# esp32.net
KiCad netlist of a schematic drawn in Altium Designer
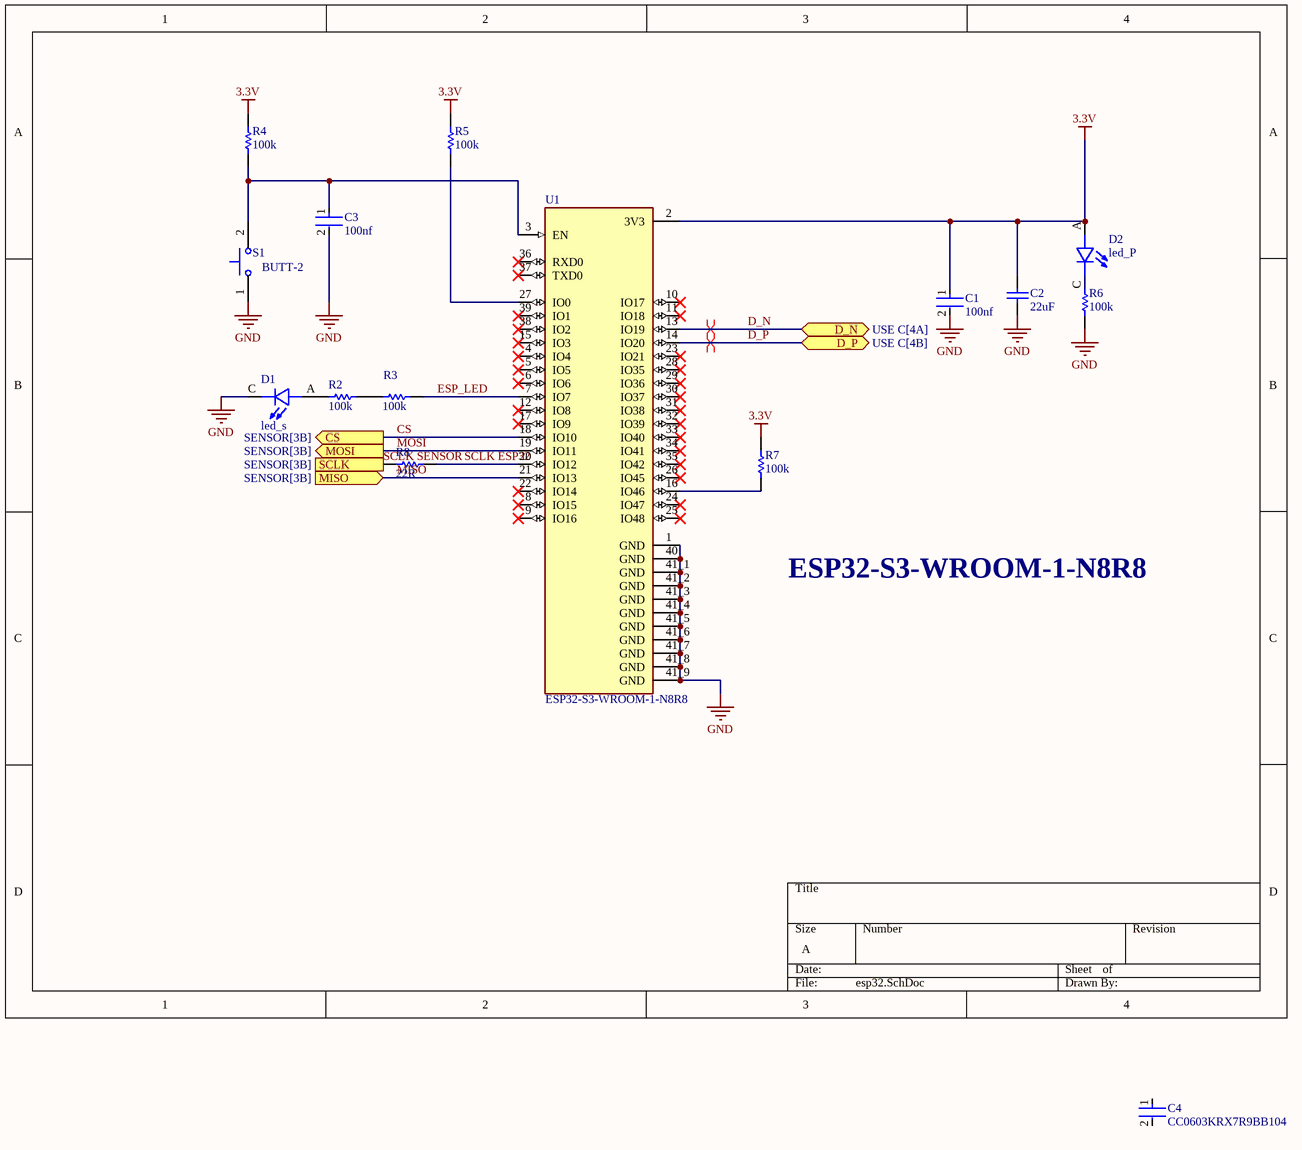
[diagram p0: esp32.SchDoc]

(export (version "E")
  (design (tool "Eeschema 10.0.6"))
  (components
    (comp (ref "C1")
      (value "100nf")
      (footprint "FP-CC0603-DA-MFG")
      (description "CAP CER 0.1UF 50V X7R 0603")
      (fields (field (name "MANUFACTURER") "YAGEO") (field (name "VOLTAGE") "50 V"))
      (libsource (lib "Altium Content Vault") (part "11868f565c42a9108669ba33697ecf6"))
    )
    (comp (ref "C2")
      (value "22uF")
      (footprint "CAPC3216X180X55ML20T25")
      (description "Chip Capacitor, 22 uF, +/- 10%, 25 V, -55 to 85 degC, 1206 (3216 Metric), RoHS, Tape and Reel")
      (fields (field (name "PARTNUMBER") "GRM31CR61E226KE15L") (field (name "TOLERANCE") "10%"))
      (libsource (lib "Altium Content Vault") (part "CAP-NP-2"))
    )
    (comp (ref "C3")
      (value "100nf")
      (footprint "FP-CC0603-DA-MFG")
      (description "CAP CER 0.1UF 50V X7R 0603")
      (fields (field (name "MANUFACTURER") "YAGEO") (field (name "VOLTAGE") "50 V"))
      (libsource (lib "Altium Content Vault") (part "11868f565c42a9108669ba33697ecf6"))
    )
    (comp (ref "C4")
      (value "CC0603KRX7R9BB104")
      (footprint "FP-CC0603-DA-MFG")
      (description "CAP CER 0.1UF 50V X7R 0603")
      (fields (field (name "MANUFACTURER") "YAGEO") (field (name "VOLTAGE") "50 V"))
      (libsource (lib "Altium Content Vault") (part "11868f565c42a9108669ba33697ecf6"))
    )
    (comp (ref "D1")
      (value "led_s")
      (footprint "LEDRD254W57D500H1070")
      (fields (field (name "MP") "L08R5000Q1") (field (name "MF") "LED Technology"))
      (libsource (lib "L08R5000Q1") (part "L08R5000Q1"))
    )
    (comp (ref "D2")
      (value "led_P")
      (footprint "LEDRD254W57D500H1070")
      (fields (field (name "MP") "L08R5000Q1") (field (name "MF") "LED Technology"))
      (libsource (lib "L08R5000Q1") (part "L08R5000Q1"))
    )
    (comp (ref "R2")
      (value "100k")
      (footprint "RESC1005X40X25NL05T10")
      (fields (field (name "PART NUMBER") "RC0402FR-07100KL") (field (name "MANUFACTURER") "Yageo / Phycomp"))
      (libsource (lib "Altium Content Vault") (part "RES"))
    )
    (comp (ref "R3")
      (value "100k")
      (footprint "RESC1005X40X25NL05T10")
      (fields (field (name "PART NUMBER") "RC0402FR-07100KL") (field (name "MANUFACTURER") "Yageo / Phycomp"))
      (libsource (lib "Altium Content Vault") (part "RES"))
    )
    (comp (ref "R4")
      (value "100k")
      (footprint "RESC1005X40X25NL05T10")
      (fields (field (name "PART NUMBER") "RC0402FR-07100KL") (field (name "MANUFACTURER") "Yageo / Phycomp"))
      (libsource (lib "Altium Content Vault") (part "RES"))
    )
    (comp (ref "R5")
      (value "100k")
      (footprint "RESC1005X40X25NL05T10")
      (fields (field (name "PART NUMBER") "RC0402FR-07100KL") (field (name "MANUFACTURER") "Yageo / Phycomp"))
      (libsource (lib "Altium Content Vault") (part "RES"))
    )
    (comp (ref "R6")
      (value "100k")
      (footprint "RESC1005X40X25NL05T10")
      (fields (field (name "PART NUMBER") "RC0402FR-07100KL") (field (name "MANUFACTURER") "Yageo / Phycomp"))
      (libsource (lib "Altium Content Vault") (part "RES"))
    )
    (comp (ref "R7")
      (value "100k")
      (footprint "RESC1005X40X25NL05T10")
      (fields (field (name "PART NUMBER") "RC0402FR-07100KL") (field (name "MANUFACTURER") "Yageo / Phycomp"))
      (libsource (lib "Altium Content Vault") (part "RES"))
    )
    (comp (ref "R8")
      (value "22R")
      (footprint "RESC1608X55X25NL10T15")
      (description "Chip Resistor, 22 Ohm, +/- 1%, 0.1 W, -55 to 155 degC, 0603 (1608 Metric), RoHS, Tape and Reel")
      (libsource (lib "Altium Content Vault") (part "RES-2"))
    )
    (comp (ref "S1")
      (value "BUTT-2")
      (footprint "SW_BUTT-2")
      (description "Tactile Switches MINI PUSH BUTTON SWITCH 2-PIN QTY. 4")
      (fields (field (name "MF") "Gravitech"))
      (libsource (lib "BUTT-2") (part "BUTT-2"))
    )
    (comp (ref "U1")
      (value "ESP32-S3-WROOM-1-N8R8")
      (footprint "XCVR_ESP32S3WROOM1N8R8")
      (description "Bluetooth, WiFi 802.11b/g/n, Bluetooth v5.0 Transceiver Module 2.4GHz PCB Trace Surface Mount")
      (fields (field (name "MF") "Espressif Systems"))
      (libsource (lib "ESP32-S3-WROOM-1-N8R8") (part "ESP32-S3-WROOM-1-N8R8"))
    )
  )
  (nets
    (net (code "1") (name "/CS") (class "Default")
      (node (ref "U1") (pin "18") (pinfunction "IO10_18") (pintype "bidirectional"))
    )
    (net (code "2") (name "/D_N") (class "Default")
      (node (ref "U1") (pin "13") (pinfunction "IO19_13") (pintype "bidirectional"))
    )
    (net (code "3") (name "/D_P") (class "Default")
      (node (ref "U1") (pin "14") (pinfunction "IO20_14") (pintype "bidirectional"))
    )
    (net (code "4") (name "/ESP_LED") (class "Default")
      (node (ref "R3") (pin "1") (pinfunction "1_1") (pintype "passive"))
      (node (ref "U1") (pin "7") (pinfunction "IO7_7") (pintype "bidirectional"))
    )
    (net (code "5") (name "/MISO") (class "Default")
      (node (ref "U1") (pin "21") (pinfunction "IO13_21") (pintype "bidirectional"))
    )
    (net (code "6") (name "/MOSI") (class "Default")
      (node (ref "U1") (pin "19") (pinfunction "IO11_19") (pintype "bidirectional"))
    )
    (net (code "7") (name "/SCLK ESP32") (class "Default")
      (node (ref "R8") (pin "2") (pinfunction "2_2") (pintype "passive"))
      (node (ref "U1") (pin "20") (pinfunction "IO12_20") (pintype "bidirectional"))
    )
    (net (code "8") (name "/SCLK SENSOR") (class "Default")
      (node (ref "R8") (pin "1") (pinfunction "1_1") (pintype "passive"))
    )
    (net (code "9") (name "3.3V") (class "Default")
      (node (ref "C1") (pin "1") (pinfunction "1_1") (pintype "passive"))
      (node (ref "C2") (pin "2") (pinfunction "2_2") (pintype "passive"))
      (node (ref "D2") (pin "A") (pinfunction "A_A") (pintype "passive"))
      (node (ref "R4") (pin "2") (pinfunction "2_2") (pintype "passive"))
      (node (ref "R5") (pin "2") (pinfunction "2_2") (pintype "passive"))
      (node (ref "R7") (pin "2") (pinfunction "2_2") (pintype "passive"))
      (node (ref "U1") (pin "2") (pinfunction "3V3_2") (pintype "power_in"))
    )
    (net (code "10") (name "GND") (class "Default")
      (node (ref "C1") (pin "2") (pinfunction "2_2") (pintype "passive"))
      (node (ref "C2") (pin "1") (pinfunction "1_1") (pintype "passive"))
      (node (ref "C3") (pin "2") (pinfunction "2_2") (pintype "passive"))
      (node (ref "D1") (pin "C") (pinfunction "C_C") (pintype "passive"))
      (node (ref "R6") (pin "1") (pinfunction "1_1") (pintype "passive"))
      (node (ref "S1") (pin "1") (pinfunction "1_1") (pintype "passive"))
      (node (ref "U1") (pin "1") (pinfunction "GND_1") (pintype "power_in"))
      (node (ref "U1") (pin "40") (pinfunction "GND_40") (pintype "power_in"))
      (node (ref "U1") (pin "41_1") (pinfunction "GND_41_1") (pintype "power_in"))
      (node (ref "U1") (pin "41_2") (pinfunction "GND_41_2") (pintype "power_in"))
      (node (ref "U1") (pin "41_3") (pinfunction "GND_41_3") (pintype "power_in"))
      (node (ref "U1") (pin "41_4") (pinfunction "GND_41_4") (pintype "power_in"))
      (node (ref "U1") (pin "41_5") (pinfunction "GND_41_5") (pintype "power_in"))
      (node (ref "U1") (pin "41_6") (pinfunction "GND_41_6") (pintype "power_in"))
      (node (ref "U1") (pin "41_7") (pinfunction "GND_41_7") (pintype "power_in"))
      (node (ref "U1") (pin "41_8") (pinfunction "GND_41_8") (pintype "power_in"))
      (node (ref "U1") (pin "41_9") (pinfunction "GND_41_9") (pintype "power_in"))
    )
    (net (code "11") (name "Net-(D1-PadA)") (class "Default")
      (node (ref "D1") (pin "A") (pinfunction "A_A") (pintype "passive"))
      (node (ref "R2") (pin "2") (pinfunction "2_2") (pintype "passive"))
    )
    (net (code "12") (name "Net-(D2-PadC)") (class "Default")
      (node (ref "D2") (pin "C") (pinfunction "C_C") (pintype "passive"))
      (node (ref "R6") (pin "2") (pinfunction "2_2") (pintype "passive"))
    )
    (net (code "13") (name "Net-(R2-Pad1)") (class "Default")
      (node (ref "R2") (pin "1") (pinfunction "1_1") (pintype "passive"))
      (node (ref "R3") (pin "2") (pinfunction "2_2") (pintype "passive"))
    )
    (net (code "14") (name "Net-(U1-EN)") (class "Default")
      (node (ref "C3") (pin "1") (pinfunction "1_1") (pintype "passive"))
      (node (ref "R4") (pin "1") (pinfunction "1_1") (pintype "passive"))
      (node (ref "S1") (pin "2") (pinfunction "2_2") (pintype "passive"))
      (node (ref "U1") (pin "3") (pinfunction "EN_3") (pintype "input"))
    )
    (net (code "15") (name "Net-(U1-IO0)") (class "Default")
      (node (ref "R5") (pin "1") (pinfunction "1_1") (pintype "passive"))
      (node (ref "U1") (pin "27") (pinfunction "IO0_27") (pintype "bidirectional"))
    )
    (net (code "16") (name "Net-(U1-IO46)") (class "Default")
      (node (ref "R7") (pin "1") (pinfunction "1_1") (pintype "passive"))
      (node (ref "U1") (pin "16") (pinfunction "IO46_16") (pintype "bidirectional"))
    )
    (net (code "17") (name "unconnected-(C4-Pad1)") (class "Default")
      (node (ref "C4") (pin "1") (pinfunction "1_1") (pintype "passive"))
    )
    (net (code "18") (name "unconnected-(C4-Pad2)") (class "Default")
      (node (ref "C4") (pin "2") (pinfunction "2_2") (pintype "passive"))
    )
    (net (code "19") (name "unconnected-(U1-IO1-Pad39)") (class "Default")
      (node (ref "U1") (pin "39") (pinfunction "IO1_39") (pintype "bidirectional+no_connect"))
    )
    (net (code "20") (name "unconnected-(U1-IO2-Pad38)") (class "Default")
      (node (ref "U1") (pin "38") (pinfunction "IO2_38") (pintype "bidirectional+no_connect"))
    )
    (net (code "21") (name "unconnected-(U1-IO3-Pad15)") (class "Default")
      (node (ref "U1") (pin "15") (pinfunction "IO3_15") (pintype "bidirectional+no_connect"))
    )
    (net (code "22") (name "unconnected-(U1-IO4-Pad4)") (class "Default")
      (node (ref "U1") (pin "4") (pinfunction "IO4_4") (pintype "bidirectional+no_connect"))
    )
    (net (code "23") (name "unconnected-(U1-IO5-Pad5)") (class "Default")
      (node (ref "U1") (pin "5") (pinfunction "IO5_5") (pintype "bidirectional+no_connect"))
    )
    (net (code "24") (name "unconnected-(U1-IO6-Pad6)") (class "Default")
      (node (ref "U1") (pin "6") (pinfunction "IO6_6") (pintype "bidirectional+no_connect"))
    )
    (net (code "25") (name "unconnected-(U1-IO8-Pad12)") (class "Default")
      (node (ref "U1") (pin "12") (pinfunction "IO8_12") (pintype "bidirectional+no_connect"))
    )
    (net (code "26") (name "unconnected-(U1-IO9-Pad17)") (class "Default")
      (node (ref "U1") (pin "17") (pinfunction "IO9_17") (pintype "bidirectional+no_connect"))
    )
    (net (code "27") (name "unconnected-(U1-IO14-Pad22)") (class "Default")
      (node (ref "U1") (pin "22") (pinfunction "IO14_22") (pintype "bidirectional+no_connect"))
    )
    (net (code "28") (name "unconnected-(U1-IO15-Pad8)") (class "Default")
      (node (ref "U1") (pin "8") (pinfunction "IO15_8") (pintype "bidirectional+no_connect"))
    )
    (net (code "29") (name "unconnected-(U1-IO16-Pad9)") (class "Default")
      (node (ref "U1") (pin "9") (pinfunction "IO16_9") (pintype "bidirectional+no_connect"))
    )
    (net (code "30") (name "unconnected-(U1-IO17-Pad10)") (class "Default")
      (node (ref "U1") (pin "10") (pinfunction "IO17_10") (pintype "bidirectional+no_connect"))
    )
    (net (code "31") (name "unconnected-(U1-IO18-Pad11)") (class "Default")
      (node (ref "U1") (pin "11") (pinfunction "IO18_11") (pintype "bidirectional+no_connect"))
    )
    (net (code "32") (name "unconnected-(U1-IO21-Pad23)") (class "Default")
      (node (ref "U1") (pin "23") (pinfunction "IO21_23") (pintype "bidirectional+no_connect"))
    )
    (net (code "33") (name "unconnected-(U1-IO35-Pad28)") (class "Default")
      (node (ref "U1") (pin "28") (pinfunction "IO35_28") (pintype "bidirectional+no_connect"))
    )
    (net (code "34") (name "unconnected-(U1-IO36-Pad29)") (class "Default")
      (node (ref "U1") (pin "29") (pinfunction "IO36_29") (pintype "bidirectional+no_connect"))
    )
    (net (code "35") (name "unconnected-(U1-IO37-Pad30)") (class "Default")
      (node (ref "U1") (pin "30") (pinfunction "IO37_30") (pintype "bidirectional+no_connect"))
    )
    (net (code "36") (name "unconnected-(U1-IO38-Pad31)") (class "Default")
      (node (ref "U1") (pin "31") (pinfunction "IO38_31") (pintype "bidirectional+no_connect"))
    )
    (net (code "37") (name "unconnected-(U1-IO39-Pad32)") (class "Default")
      (node (ref "U1") (pin "32") (pinfunction "IO39_32") (pintype "bidirectional+no_connect"))
    )
    (net (code "38") (name "unconnected-(U1-IO40-Pad33)") (class "Default")
      (node (ref "U1") (pin "33") (pinfunction "IO40_33") (pintype "bidirectional+no_connect"))
    )
    (net (code "39") (name "unconnected-(U1-IO41-Pad34)") (class "Default")
      (node (ref "U1") (pin "34") (pinfunction "IO41_34") (pintype "bidirectional+no_connect"))
    )
    (net (code "40") (name "unconnected-(U1-IO42-Pad35)") (class "Default")
      (node (ref "U1") (pin "35") (pinfunction "IO42_35") (pintype "bidirectional+no_connect"))
    )
    (net (code "41") (name "unconnected-(U1-IO45-Pad26)") (class "Default")
      (node (ref "U1") (pin "26") (pinfunction "IO45_26") (pintype "bidirectional+no_connect"))
    )
    (net (code "42") (name "unconnected-(U1-IO47-Pad24)") (class "Default")
      (node (ref "U1") (pin "24") (pinfunction "IO47_24") (pintype "bidirectional+no_connect"))
    )
    (net (code "43") (name "unconnected-(U1-IO48-Pad25)") (class "Default")
      (node (ref "U1") (pin "25") (pinfunction "IO48_25") (pintype "bidirectional+no_connect"))
    )
    (net (code "44") (name "unconnected-(U1-RXD0-Pad36)") (class "Default")
      (node (ref "U1") (pin "36") (pinfunction "RXD0_36") (pintype "bidirectional+no_connect"))
    )
    (net (code "45") (name "unconnected-(U1-TXD0-Pad37)") (class "Default")
      (node (ref "U1") (pin "37") (pinfunction "TXD0_37") (pintype "bidirectional+no_connect"))
    )
  )
)
